# Power-Supplies.net
KiCad netlist of a schematic drawn in Altium Designer
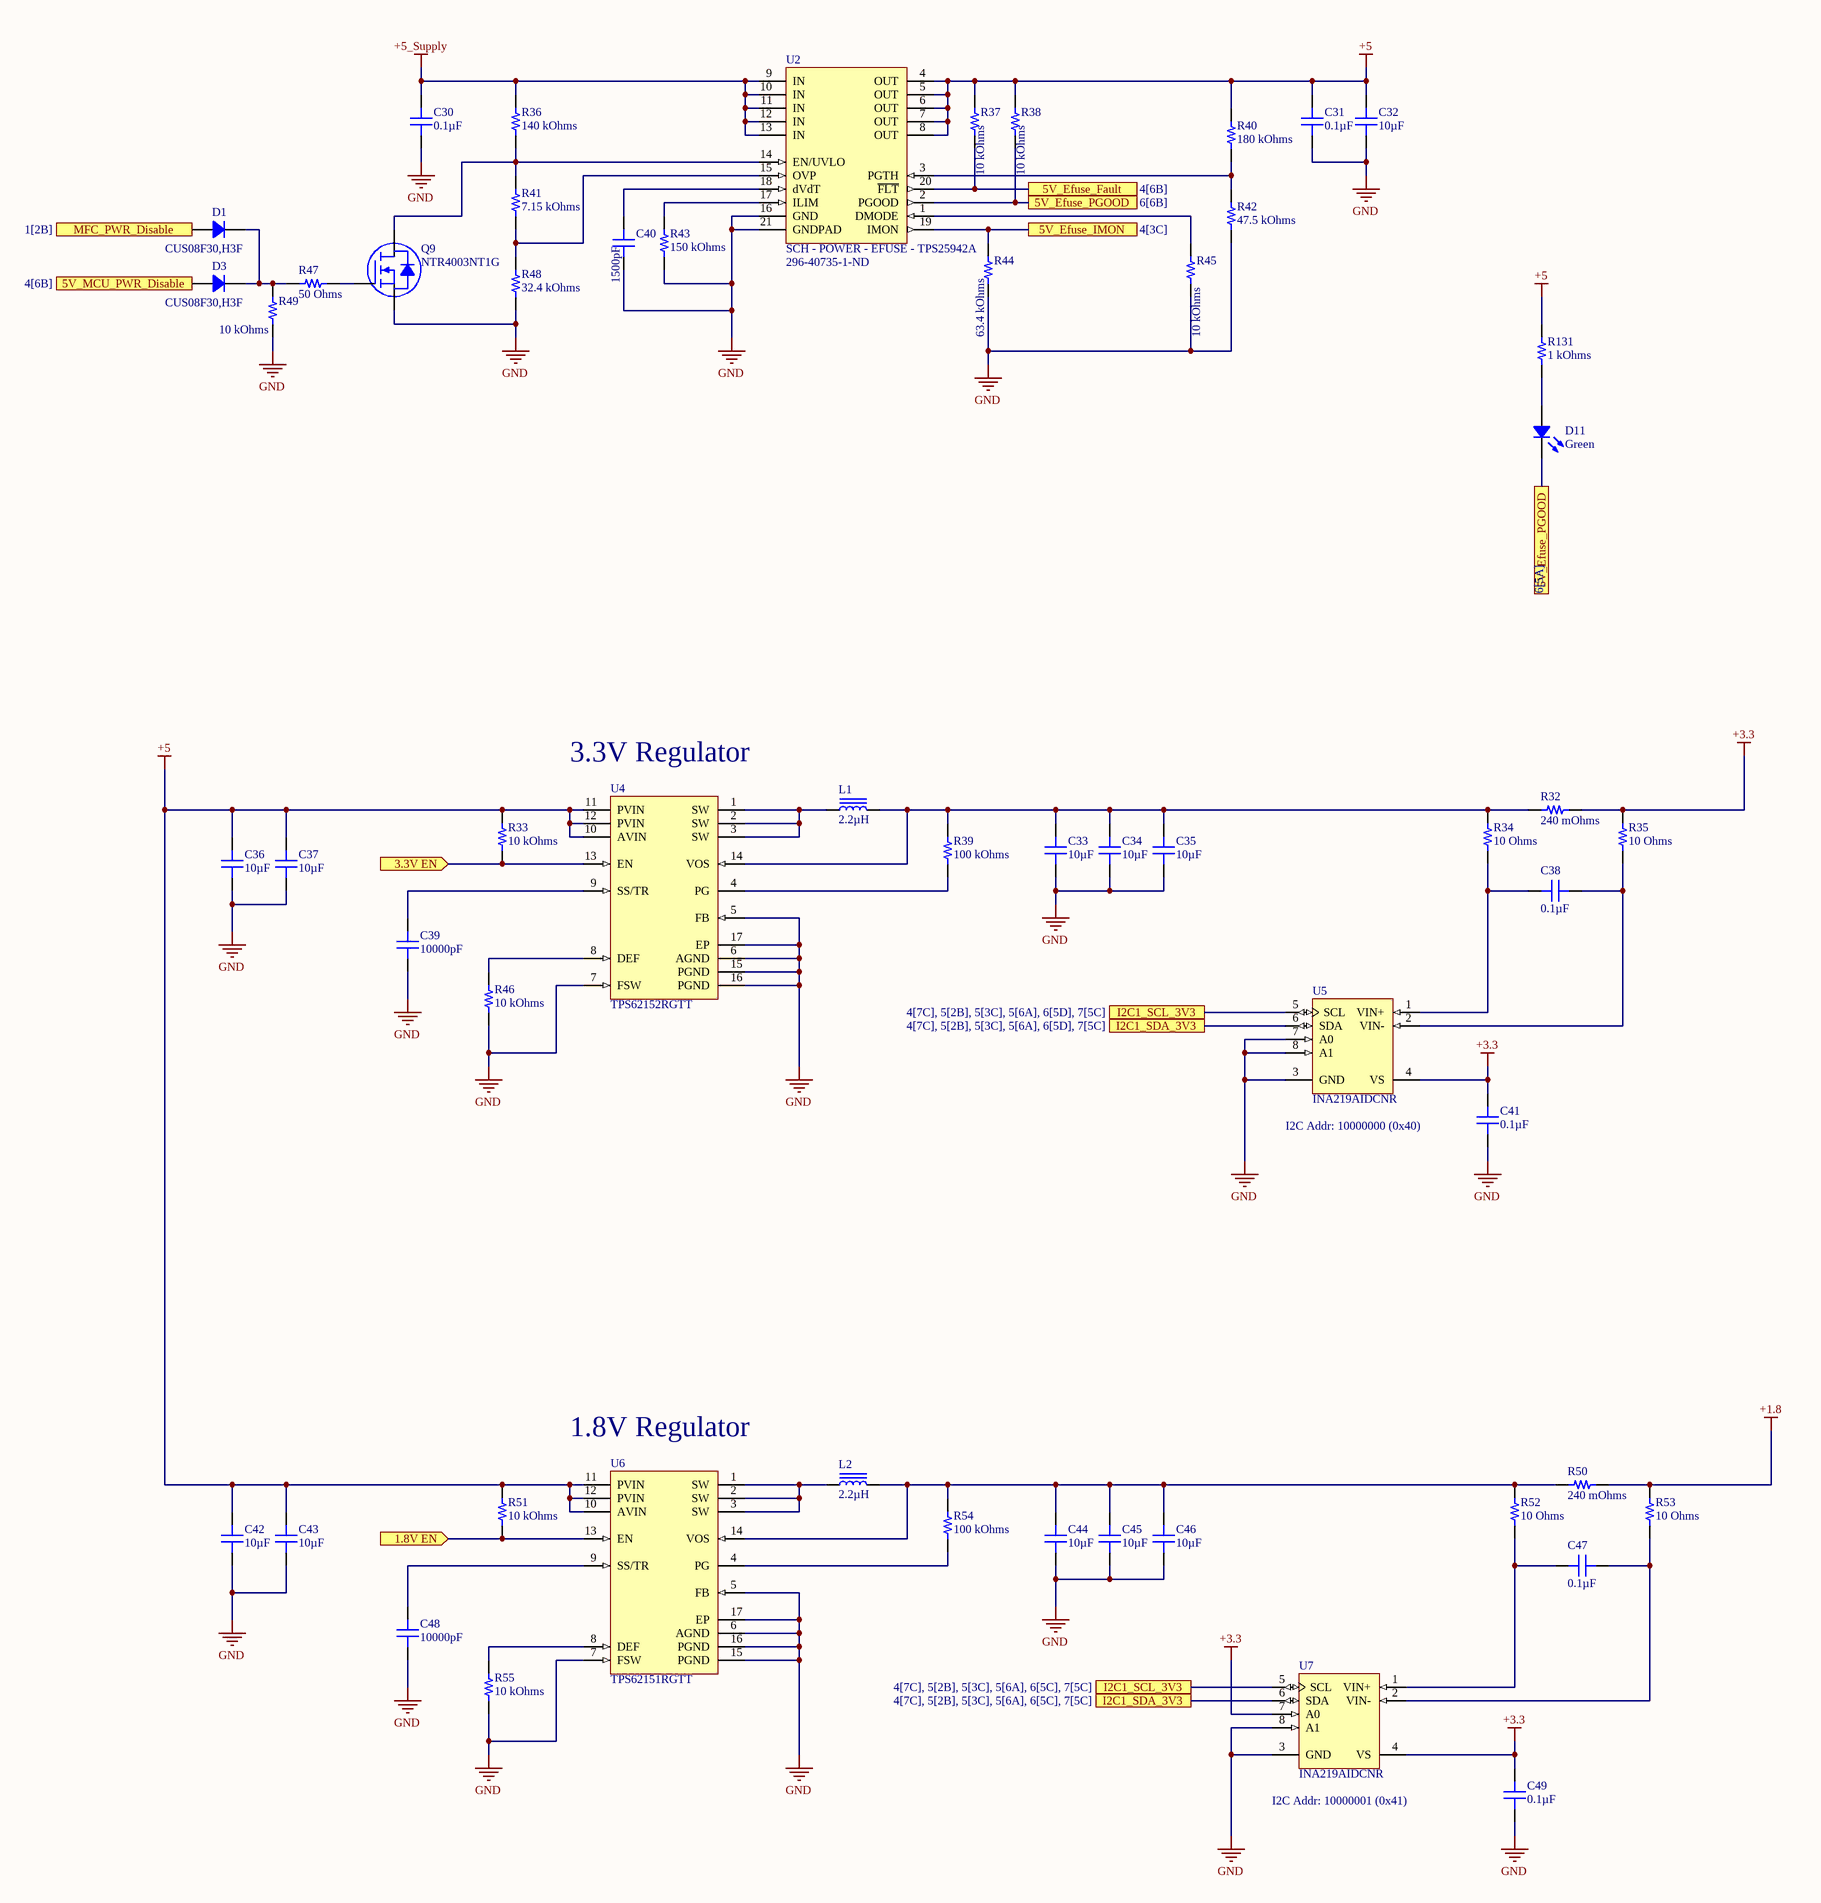
[diagram p0: Power-Supplies.SchDoc]

(export (version "E")
  (design (tool "Eeschema 10.0.6"))
  (components
    (comp (ref "C30")
      (value "0.1µF")
      (footprint "CAP 0603_1608")
      (description "CAP CER 0.1UF 25V X7R 0603")
      (fields
        (field (name "PART NUMBER") "CL10B104KA8WPNC")
        (field (name "MANUFACTURER") "Samsung Electro-Mechanics")
      )
      (libsource (lib "Celestial Altium Library - altium_library") (part "Capacitor"))
    )
    (comp (ref "C31")
      (value "0.1µF")
      (footprint "CAP 0603_1608")
      (description "CAP CER 0.1UF 25V X7R 0603")
      (fields
        (field (name "PART NUMBER") "CL10B104KA8WPNC")
        (field (name "MANUFACTURER") "Samsung Electro-Mechanics")
      )
      (libsource (lib "Celestial Altium Library - altium_library") (part "Capacitor"))
    )
    (comp (ref "C32")
      (value "10µF")
      (footprint "CAP 0805_2012")
      (description "CAP CER 10UF 16V X5R 0805")
      (fields (field (name "PART NUMBER") "CC0805KKX5R7BB106") (field (name "MANUFACTURER") "Yageo"))
      (libsource (lib "Celestial Altium Library - altium_library") (part "Capacitor"))
    )
    (comp (ref "C33")
      (value "10µF")
      (footprint "CAP 0805_2012")
      (description "CAP CER 10UF 16V X5R 0805")
      (fields (field (name "PART NUMBER") "CC0805KKX5R7BB106") (field (name "MANUFACTURER") "Yageo"))
      (libsource (lib "Celestial Altium Library - altium_library") (part "Capacitor"))
    )
    (comp (ref "C34")
      (value "10µF")
      (footprint "CAP 0805_2012")
      (description "CAP CER 10UF 16V X5R 0805")
      (fields (field (name "PART NUMBER") "CC0805KKX5R7BB106") (field (name "MANUFACTURER") "Yageo"))
      (libsource (lib "Celestial Altium Library - altium_library") (part "Capacitor"))
    )
    (comp (ref "C35")
      (value "10µF")
      (footprint "CAP 0805_2012")
      (description "CAP CER 10UF 16V X5R 0805")
      (fields (field (name "PART NUMBER") "CC0805KKX5R7BB106") (field (name "MANUFACTURER") "Yageo"))
      (libsource (lib "Celestial Altium Library - altium_library") (part "Capacitor"))
    )
    (comp (ref "C36")
      (value "10µF")
      (footprint "CAP 0805_2012")
      (description "CAP CER 10UF 16V X5R 0805")
      (fields (field (name "PART NUMBER") "CC0805KKX5R7BB106") (field (name "MANUFACTURER") "Yageo"))
      (libsource (lib "Celestial Altium Library - altium_library") (part "Capacitor"))
    )
    (comp (ref "C37")
      (value "10µF")
      (footprint "CAP 0805_2012")
      (description "CAP CER 10UF 16V X5R 0805")
      (fields (field (name "PART NUMBER") "CC0805KKX5R7BB106") (field (name "MANUFACTURER") "Yageo"))
      (libsource (lib "Celestial Altium Library - altium_library") (part "Capacitor"))
    )
    (comp (ref "C38")
      (value "0.1µF")
      (footprint "CAP 0603_1608")
      (description "CAP CER 0.1UF 25V X7R 0603")
      (fields
        (field (name "PART NUMBER") "CL10B104KA8WPNC")
        (field (name "MANUFACTURER") "Samsung Electro-Mechanics")
      )
      (libsource (lib "Celestial Altium Library - altium_library") (part "Capacitor"))
    )
    (comp (ref "C39")
      (value "10000pF")
      (footprint "CAP 0603_1608")
      (description "CAP CER 10000PF 16V X7R 0603")
      (fields (field (name "PART NUMBER") "C0603S103K4RACTU") (field (name "MANUFACTURER") "KEMET"))
      (libsource (lib "Celestial Altium Library - altium_library") (part "Capacitor"))
    )
    (comp (ref "C40")
      (value "1500pF")
      (footprint "CAP 0603_1608")
      (description "CAP CER 1500PF 25V X7R 0603")
      (fields (field (name "PART NUMBER") "CC0603JRX7R8BB152") (field (name "MANUFACTURER") "Yageo"))
      (libsource (lib "Celestial Altium Library - altium_library") (part "Capacitor"))
    )
    (comp (ref "C41")
      (value "0.1µF")
      (footprint "CAP 0603_1608")
      (description "CAP CER 0.1UF 25V X7R 0603")
      (fields
        (field (name "PART NUMBER") "CL10B104KA8WPNC")
        (field (name "MANUFACTURER") "Samsung Electro-Mechanics")
      )
      (libsource (lib "Celestial Altium Library - altium_library") (part "Capacitor"))
    )
    (comp (ref "C42")
      (value "10µF")
      (footprint "CAP 0805_2012")
      (description "CAP CER 10UF 16V X5R 0805")
      (fields (field (name "PART NUMBER") "CC0805KKX5R7BB106") (field (name "MANUFACTURER") "Yageo"))
      (libsource (lib "Celestial Altium Library - altium_library") (part "Capacitor"))
    )
    (comp (ref "C43")
      (value "10µF")
      (footprint "CAP 0805_2012")
      (description "CAP CER 10UF 16V X5R 0805")
      (fields (field (name "PART NUMBER") "CC0805KKX5R7BB106") (field (name "MANUFACTURER") "Yageo"))
      (libsource (lib "Celestial Altium Library - altium_library") (part "Capacitor"))
    )
    (comp (ref "C44")
      (value "10µF")
      (footprint "CAP 0805_2012")
      (description "CAP CER 10UF 16V X5R 0805")
      (fields (field (name "PART NUMBER") "CC0805KKX5R7BB106") (field (name "MANUFACTURER") "Yageo"))
      (libsource (lib "Celestial Altium Library - altium_library") (part "Capacitor"))
    )
    (comp (ref "C45")
      (value "10µF")
      (footprint "CAP 0805_2012")
      (description "CAP CER 10UF 16V X5R 0805")
      (fields (field (name "PART NUMBER") "CC0805KKX5R7BB106") (field (name "MANUFACTURER") "Yageo"))
      (libsource (lib "Celestial Altium Library - altium_library") (part "Capacitor"))
    )
    (comp (ref "C46")
      (value "10µF")
      (footprint "CAP 0805_2012")
      (description "CAP CER 10UF 16V X5R 0805")
      (fields (field (name "PART NUMBER") "CC0805KKX5R7BB106") (field (name "MANUFACTURER") "Yageo"))
      (libsource (lib "Celestial Altium Library - altium_library") (part "Capacitor"))
    )
    (comp (ref "C47")
      (value "0.1µF")
      (footprint "CAP 0603_1608")
      (description "CAP CER 0.1UF 25V X7R 0603")
      (fields
        (field (name "PART NUMBER") "CL10B104KA8WPNC")
        (field (name "MANUFACTURER") "Samsung Electro-Mechanics")
      )
      (libsource (lib "Celestial Altium Library - altium_library") (part "Capacitor"))
    )
    (comp (ref "C48")
      (value "10000pF")
      (footprint "CAP 0603_1608")
      (description "CAP CER 10000PF 16V X7R 0603")
      (fields (field (name "PART NUMBER") "C0603S103K4RACTU") (field (name "MANUFACTURER") "KEMET"))
      (libsource (lib "Celestial Altium Library - altium_library") (part "Capacitor"))
    )
    (comp (ref "C49")
      (value "0.1µF")
      (footprint "CAP 0603_1608")
      (description "CAP CER 0.1UF 25V X7R 0603")
      (fields
        (field (name "PART NUMBER") "CL10B104KA8WPNC")
        (field (name "MANUFACTURER") "Samsung Electro-Mechanics")
      )
      (libsource (lib "Celestial Altium Library - altium_library") (part "Capacitor"))
    )
    (comp (ref "D1")
      (value "CUS08F30,H3F")
      (footprint "SOD323")
      (description "DIODE SCHOTTKY 30V 800MA USC")
      (fields (field (name "MANUFACTURER") "Toshiba Semiconductor and Storage"))
      (libsource (lib "Celestial Altium Library - altium_library") (part "Diode"))
    )
    (comp (ref "D3")
      (value "CUS08F30,H3F")
      (footprint "SOD323")
      (description "DIODE SCHOTTKY 30V 800MA USC")
      (fields (field (name "MANUFACTURER") "Toshiba Semiconductor and Storage"))
      (libsource (lib "Celestial Altium Library - altium_library") (part "Diode"))
    )
    (comp (ref "D11")
      (value "Green")
      (footprint "LED 0603_1608 GREEN")
      (description "LED GREEN CLEAR CHIP SMD")
      (fields (field (name "PART NUMBER") "LTST-C193KGKT-5A") (field (name "MANUFACTURER") "Lite-On Inc."))
      (libsource (lib "Celestial Altium Library - altium_library") (part "LED"))
    )
    (comp (ref "L1")
      (value "2.2µH")
      (footprint "BOURNS SRN4018")
      (description "FIXED IND 2.2UH 2.9A 44 MOHM SMD")
      (fields (field (name "PART NUMBER") "SRN4018-2R2M") (field (name "MANUFACTURER") "Bourns Inc."))
      (libsource (lib "Celestial Altium Library - altium_library") (part "Inductor"))
    )
    (comp (ref "L2")
      (value "2.2µH")
      (footprint "BOURNS SRN4018")
      (description "FIXED IND 2.2UH 2.9A 44 MOHM SMD")
      (fields (field (name "PART NUMBER") "SRN4018-2R2M") (field (name "MANUFACTURER") "Bourns Inc."))
      (libsource (lib "Celestial Altium Library - altium_library") (part "Inductor"))
    )
    (comp (ref "Q9")
      (value "NTR4003NT1G")
      (footprint "ON SEMI SOT-23-3")
      (description "MOSFET N-CH 30V 500MA SOT-23")
      (fields (field (name "MANUFACTURER") "ON Semiconductor"))
      (libsource (lib "Celestial Altium Library - altium_library") (part "ON SEMI MOSFET N-CH SOT-23-3"))
    )
    (comp (ref "R32")
      (value "240 mOhms")
      (footprint "RES 0805_2012")
      (description "RES 0.24 OHM 1% 1/2W 0805")
      (fields
        (field (name "PART NUMBER") "ERJ-6DQFR24V")
        (field (name "MANUFACTURER") "Panasonic Electronic Components")
      )
      (libsource (lib "Celestial Altium Library - altium_library") (part "Resistor"))
    )
    (comp (ref "R33")
      (value "10 kOhms")
      (footprint "RES 0603_1608")
      (description "RES 10K OHM 5% 1/10W 0603")
      (fields
        (field (name "PART NUMBER") "RMCF0603JT10K0")
        (field (name "MANUFACTURER") "Stackpole Electronics Inc")
      )
      (libsource (lib "Celestial Altium Library - altium_library") (part "Resistor"))
    )
    (comp (ref "R34")
      (value "10 Ohms")
      (footprint "RES 0603_1608")
      (description "CRGCQ 0603 10R 1%")
      (fields
        (field (name "PART NUMBER") "CRGCQ0603F10R")
        (field (name "MANUFACTURER") "TE Connectivity Passive Product")
      )
      (libsource (lib "Celestial Altium Library - altium_library") (part "Resistor"))
    )
    (comp (ref "R35")
      (value "10 Ohms")
      (footprint "RES 0603_1608")
      (description "CRGCQ 0603 10R 1%")
      (fields
        (field (name "PART NUMBER") "CRGCQ0603F10R")
        (field (name "MANUFACTURER") "TE Connectivity Passive Product")
      )
      (libsource (lib "Celestial Altium Library - altium_library") (part "Resistor"))
    )
    (comp (ref "R36")
      (value "140 kOhms")
      (footprint "RES 0603_1608")
      (description "RES SMD 140K OHM 0.1% 1/10W 0603")
      (fields (field (name "PART NUMBER") "RT0603BRE07140KL") (field (name "MANUFACTURER") "Yageo"))
      (libsource (lib "Celestial Altium Library - altium_library") (part "Resistor"))
    )
    (comp (ref "R37")
      (value "10 kOhms")
      (footprint "RES 0603_1608")
      (description "RES 10K OHM 5% 1/10W 0603")
      (fields
        (field (name "PART NUMBER") "RMCF0603JT10K0")
        (field (name "MANUFACTURER") "Stackpole Electronics Inc")
      )
      (libsource (lib "Celestial Altium Library - altium_library") (part "Resistor"))
    )
    (comp (ref "R38")
      (value "10 kOhms")
      (footprint "RES 0603_1608")
      (description "RES 10K OHM 5% 1/10W 0603")
      (fields
        (field (name "PART NUMBER") "RMCF0603JT10K0")
        (field (name "MANUFACTURER") "Stackpole Electronics Inc")
      )
      (libsource (lib "Celestial Altium Library - altium_library") (part "Resistor"))
    )
    (comp (ref "R39")
      (value "100 kOhms")
      (footprint "RES 0603_1608")
      (description "RES SMD 100K OHM 5% 1/10W 0603")
      (fields (field (name "PART NUMBER") "RC0603JR-10100KL") (field (name "MANUFACTURER") "Yageo"))
      (libsource (lib "Celestial Altium Library - altium_library") (part "Resistor"))
    )
    (comp (ref "R40")
      (value "180 kOhms")
      (footprint "RES 0603_1608")
      (description "RES 180K OHM 1% 1/10W 0603")
      (fields
        (field (name "PART NUMBER") "RMCF0603FT180K")
        (field (name "MANUFACTURER") "Stackpole Electronics Inc")
      )
      (libsource (lib "Celestial Altium Library - altium_library") (part "Resistor"))
    )
    (comp (ref "R41")
      (value "7.15 kOhms")
      (footprint "RES 0603_1608")
      (description "RES SMD 7.15K OHM 0.1% 1/5W 0603")
      (fields
        (field (name "PART NUMBER") "ERJ-PB3B7151V")
        (field (name "MANUFACTURER") "Panasonic Electronic Components")
      )
      (libsource (lib "Celestial Altium Library - altium_library") (part "Resistor"))
    )
    (comp (ref "R42")
      (value "47.5 kOhms")
      (footprint "RES 0603_1608")
      (description "RES 47.5K OHM 1% 1/10W 0603")
      (fields
        (field (name "PART NUMBER") "RMCF0603FG47K5")
        (field (name "MANUFACTURER") "Stackpole Electronics Inc")
      )
      (libsource (lib "Celestial Altium Library - altium_library") (part "Resistor"))
    )
    (comp (ref "R43")
      (value "150 kOhms")
      (footprint "RES 0603_1608")
      (description "RES 150K OHM 1% 1/10W 0603")
      (fields
        (field (name "PART NUMBER") "RMCF0603FG150K")
        (field (name "MANUFACTURER") "Stackpole Electronics Inc")
      )
      (libsource (lib "Celestial Altium Library - altium_library") (part "Resistor"))
    )
    (comp (ref "R44")
      (value "63.4 kOhms")
      (footprint "RES 0603_1608")
      (description "RES 63.4K OHM 1% 1/10W 0603")
      (fields
        (field (name "PART NUMBER") "RMCF0603FT63K4")
        (field (name "MANUFACTURER") "Stackpole Electronics Inc")
      )
      (libsource (lib "Celestial Altium Library - altium_library") (part "Resistor"))
    )
    (comp (ref "R45")
      (value "10 kOhms")
      (footprint "RES 0603_1608")
      (description "RES 10K OHM 5% 1/10W 0603")
      (fields
        (field (name "PART NUMBER") "RMCF0603JT10K0")
        (field (name "MANUFACTURER") "Stackpole Electronics Inc")
      )
      (libsource (lib "Celestial Altium Library - altium_library") (part "Resistor"))
    )
    (comp (ref "R46")
      (value "10 kOhms")
      (footprint "RES 0603_1608")
      (description "RES 10K OHM 5% 1/10W 0603")
      (fields
        (field (name "PART NUMBER") "RMCF0603JT10K0")
        (field (name "MANUFACTURER") "Stackpole Electronics Inc")
      )
      (libsource (lib "Celestial Altium Library - altium_library") (part "Resistor"))
    )
    (comp (ref "R47")
      (value "50 Ohms")
      (footprint "RES 0603_1608")
      (description "RES SMD 50 OHM 1% 1/10W 0603")
      (fields (field (name "PART NUMBER") "CRCW060350R0FKEA") (field (name "MANUFACTURER") "Vishay Dale"))
      (libsource (lib "Celestial Altium Library - altium_library") (part "Resistor"))
    )
    (comp (ref "R48")
      (value "32.4 kOhms")
      (footprint "RES 0603_1608")
      (description "RES SMD 32.4K OHM 0.1% 1/5W 0603")
      (fields
        (field (name "PART NUMBER") "ERJ-PB3B3242V")
        (field (name "MANUFACTURER") "Panasonic Electronic Components")
      )
      (libsource (lib "Celestial Altium Library - altium_library") (part "Resistor"))
    )
    (comp (ref "R49")
      (value "10 kOhms")
      (footprint "RES 0603_1608")
      (description "RES 10K OHM 5% 1/10W 0603")
      (fields
        (field (name "PART NUMBER") "RMCF0603JT10K0")
        (field (name "MANUFACTURER") "Stackpole Electronics Inc")
      )
      (libsource (lib "Celestial Altium Library - altium_library") (part "Resistor"))
    )
    (comp (ref "R50")
      (value "240 mOhms")
      (footprint "RES 0805_2012")
      (description "RES 0.24 OHM 1% 1/2W 0805")
      (fields
        (field (name "PART NUMBER") "ERJ-6DQFR24V")
        (field (name "MANUFACTURER") "Panasonic Electronic Components")
      )
      (libsource (lib "Celestial Altium Library - altium_library") (part "Resistor"))
    )
    (comp (ref "R51")
      (value "10 kOhms")
      (footprint "RES 0603_1608")
      (description "RES 10K OHM 5% 1/10W 0603")
      (fields
        (field (name "PART NUMBER") "RMCF0603JT10K0")
        (field (name "MANUFACTURER") "Stackpole Electronics Inc")
      )
      (libsource (lib "Celestial Altium Library - altium_library") (part "Resistor"))
    )
    (comp (ref "R52")
      (value "10 Ohms")
      (footprint "RES 0603_1608")
      (description "CRGCQ 0603 10R 1%")
      (fields
        (field (name "PART NUMBER") "CRGCQ0603F10R")
        (field (name "MANUFACTURER") "TE Connectivity Passive Product")
      )
      (libsource (lib "Celestial Altium Library - altium_library") (part "Resistor"))
    )
    (comp (ref "R53")
      (value "10 Ohms")
      (footprint "RES 0603_1608")
      (description "CRGCQ 0603 10R 1%")
      (fields
        (field (name "PART NUMBER") "CRGCQ0603F10R")
        (field (name "MANUFACTURER") "TE Connectivity Passive Product")
      )
      (libsource (lib "Celestial Altium Library - altium_library") (part "Resistor"))
    )
    (comp (ref "R54")
      (value "100 kOhms")
      (footprint "RES 0603_1608")
      (description "RES SMD 100K OHM 5% 1/10W 0603")
      (fields (field (name "PART NUMBER") "RC0603JR-10100KL") (field (name "MANUFACTURER") "Yageo"))
      (libsource (lib "Celestial Altium Library - altium_library") (part "Resistor"))
    )
    (comp (ref "R55")
      (value "10 kOhms")
      (footprint "RES 0603_1608")
      (description "RES 10K OHM 5% 1/10W 0603")
      (fields
        (field (name "PART NUMBER") "RMCF0603JT10K0")
        (field (name "MANUFACTURER") "Stackpole Electronics Inc")
      )
      (libsource (lib "Celestial Altium Library - altium_library") (part "Resistor"))
    )
    (comp (ref "R131")
      (value "1 kOhms")
      (footprint "RES 0603_1608")
      (description "RES 1K OHM 1% 1/8W 0603")
      (fields
        (field (name "PART NUMBER") "RNCP0603FTD1K00")
        (field (name "MANUFACTURER") "Stackpole Electronics Inc")
      )
      (libsource (lib "Celestial Altium Library - altium_library") (part "Resistor"))
    )
    (comp (ref "U2")
      (value "SCH - POWER - EFUSE - TPS25942A")
      (footprint "PCB - LEADLESS - QFN - TI 20-WQFN")
      (fields (field (name "SUPPLIER PART NUMBER 1") "296-40735-1-ND"))
      (libsource (lib "HAB_ICs") (part "SCH - POWER - EFUSE - TPS25942A"))
    )
    (comp (ref "U4")
      (value "TPS62152RGTT")
      (footprint "RGT0016C_V")
      (fields (field (name "MANUFACTURER") "Texas Instruments"))
      (libsource (lib "Altium Content Vault") (part "TI-TPS62152RGT16-1700X1700TP"))
    )
    (comp (ref "U5")
      (value "INA219AIDCNR")
      (footprint "DCN0008A_M")
      (fields (field (name "MANUFACTURER") "Texas Instruments"))
      (libsource (lib "Altium Content Vault") (part "TI-INA219DCN8"))
    )
    (comp (ref "U6")
      (value "TPS62151RGTT")
      (footprint "RGT0016C_V")
      (fields (field (name "MANUFACTURER") "Texas Instruments"))
      (libsource (lib "Altium Content Vault") (part "TI-TPS62151RGT16-1700X1700TP"))
    )
    (comp (ref "U7")
      (value "INA219AIDCNR")
      (footprint "DCN0008A_M")
      (fields (field (name "MANUFACTURER") "Texas Instruments"))
      (libsource (lib "Altium Content Vault") (part "TI-INA219DCN8"))
    )
  )
  (nets
    (net (code "1") (name "+1.8") (class "Default")
      (node (ref "R50") (pin "2") (pinfunction "2_2") (pintype "passive"))
      (node (ref "R53") (pin "2") (pinfunction "2_2") (pintype "passive"))
    )
    (net (code "2") (name "+3.3") (class "Default")
      (node (ref "C41") (pin "2") (pinfunction "2_2") (pintype "passive"))
      (node (ref "C49") (pin "2") (pinfunction "2_2") (pintype "passive"))
      (node (ref "R32") (pin "2") (pinfunction "2_2") (pintype "passive"))
      (node (ref "R35") (pin "2") (pinfunction "2_2") (pintype "passive"))
      (node (ref "U5") (pin "4") (pinfunction "VS_4") (pintype "power_in"))
      (node (ref "U7") (pin "4") (pinfunction "VS_4") (pintype "power_in"))
      (node (ref "U7") (pin "7") (pinfunction "A0_7") (pintype "input"))
    )
    (net (code "3") (name "+5") (class "Default")
      (node (ref "C31") (pin "2") (pinfunction "2_2") (pintype "passive"))
      (node (ref "C32") (pin "2") (pinfunction "2_2") (pintype "passive"))
      (node (ref "C36") (pin "2") (pinfunction "2_2") (pintype "passive"))
      (node (ref "C37") (pin "2") (pinfunction "2_2") (pintype "passive"))
      (node (ref "C42") (pin "2") (pinfunction "2_2") (pintype "passive"))
      (node (ref "C43") (pin "2") (pinfunction "2_2") (pintype "passive"))
      (node (ref "R131") (pin "1") (pinfunction "1_1") (pintype "passive"))
      (node (ref "R33") (pin "2") (pinfunction "2_2") (pintype "passive"))
      (node (ref "R37") (pin "2") (pinfunction "2_2") (pintype "passive"))
      (node (ref "R38") (pin "2") (pinfunction "2_2") (pintype "passive"))
      (node (ref "R40") (pin "2") (pinfunction "2_2") (pintype "passive"))
      (node (ref "R51") (pin "2") (pinfunction "2_2") (pintype "passive"))
      (node (ref "U2") (pin "4") (pinfunction "OUT_4") (pintype "power_in"))
      (node (ref "U2") (pin "5") (pinfunction "OUT_5") (pintype "power_in"))
      (node (ref "U2") (pin "6") (pinfunction "OUT_6") (pintype "power_in"))
      (node (ref "U2") (pin "7") (pinfunction "OUT_7") (pintype "power_in"))
      (node (ref "U2") (pin "8") (pinfunction "OUT_8") (pintype "power_in"))
      (node (ref "U4") (pin "10") (pinfunction "AVIN_10") (pintype "power_in"))
      (node (ref "U4") (pin "11") (pinfunction "PVIN_11") (pintype "power_in"))
      (node (ref "U4") (pin "12") (pinfunction "PVIN_12") (pintype "power_in"))
      (node (ref "U6") (pin "10") (pinfunction "AVIN_10") (pintype "power_in"))
      (node (ref "U6") (pin "11") (pinfunction "PVIN_11") (pintype "power_in"))
      (node (ref "U6") (pin "12") (pinfunction "PVIN_12") (pintype "power_in"))
    )
    (net (code "4") (name "+5_Supply") (class "Default")
      (node (ref "C30") (pin "2") (pinfunction "2_2") (pintype "passive"))
      (node (ref "R36") (pin "2") (pinfunction "2_2") (pintype "passive"))
      (node (ref "U2") (pin "10") (pinfunction "IN_10") (pintype "power_in"))
      (node (ref "U2") (pin "11") (pinfunction "IN_11") (pintype "power_in"))
      (node (ref "U2") (pin "12") (pinfunction "IN_12") (pintype "power_in"))
      (node (ref "U2") (pin "13") (pinfunction "IN_13") (pintype "power_in"))
      (node (ref "U2") (pin "9") (pinfunction "IN_9") (pintype "power_in"))
    )
    (net (code "5") (name "/1.8V EN") (class "Default")
      (node (ref "R51") (pin "1") (pinfunction "1_1") (pintype "passive"))
      (node (ref "U6") (pin "13") (pinfunction "EN_13") (pintype "input"))
    )
    (net (code "6") (name "/3.3V EN") (class "Default")
      (node (ref "R33") (pin "1") (pinfunction "1_1") (pintype "passive"))
      (node (ref "U4") (pin "13") (pinfunction "EN_13") (pintype "input"))
    )
    (net (code "7") (name "/5V_Efuse_Fault") (class "Default")
      (node (ref "R37") (pin "1") (pinfunction "1_1") (pintype "passive"))
      (node (ref "U2") (pin "20") (pinfunction "~{FLT}_20") (pintype "output"))
    )
    (net (code "8") (name "/5V_Efuse_IMON") (class "Default")
      (node (ref "R44") (pin "2") (pinfunction "2_2") (pintype "passive"))
      (node (ref "U2") (pin "19") (pinfunction "IMON_19") (pintype "output"))
    )
    (net (code "9") (name "/5V_Efuse_PGOOD") (class "Default")
      (node (ref "D11") (pin "2") (pinfunction "2_2") (pintype "passive"))
      (node (ref "R38") (pin "1") (pinfunction "1_1") (pintype "passive"))
      (node (ref "U2") (pin "2") (pinfunction "PGOOD_2") (pintype "output"))
    )
    (net (code "10") (name "/5V_MCU_PWR_Disable") (class "Default")
      (node (ref "D3") (pin "1") (pinfunction "1_1") (pintype "passive"))
    )
    (net (code "11") (name "/I2C1_SCL_3V3") (class "Default")
      (node (ref "U5") (pin "5") (pinfunction "SCL_5") (pintype "bidirectional"))
      (node (ref "U7") (pin "5") (pinfunction "SCL_5") (pintype "bidirectional"))
    )
    (net (code "12") (name "/I2C1_SDA_3V3") (class "Default")
      (node (ref "U5") (pin "6") (pinfunction "SDA_6") (pintype "bidirectional"))
      (node (ref "U7") (pin "6") (pinfunction "SDA_6") (pintype "bidirectional"))
    )
    (net (code "13") (name "/MFC_PWR_Disable") (class "Default")
      (node (ref "D1") (pin "1") (pinfunction "1_1") (pintype "passive"))
    )
    (net (code "14") (name "GND") (class "Default")
      (node (ref "C30") (pin "1") (pinfunction "1_1") (pintype "passive"))
      (node (ref "C31") (pin "1") (pinfunction "1_1") (pintype "passive"))
      (node (ref "C32") (pin "1") (pinfunction "1_1") (pintype "passive"))
      (node (ref "C33") (pin "1") (pinfunction "1_1") (pintype "passive"))
      (node (ref "C34") (pin "1") (pinfunction "1_1") (pintype "passive"))
      (node (ref "C35") (pin "1") (pinfunction "1_1") (pintype "passive"))
      (node (ref "C36") (pin "1") (pinfunction "1_1") (pintype "passive"))
      (node (ref "C37") (pin "1") (pinfunction "1_1") (pintype "passive"))
      (node (ref "C39") (pin "1") (pinfunction "1_1") (pintype "passive"))
      (node (ref "C40") (pin "1") (pinfunction "1_1") (pintype "passive"))
      (node (ref "C41") (pin "1") (pinfunction "1_1") (pintype "passive"))
      (node (ref "C42") (pin "1") (pinfunction "1_1") (pintype "passive"))
      (node (ref "C43") (pin "1") (pinfunction "1_1") (pintype "passive"))
      (node (ref "C44") (pin "1") (pinfunction "1_1") (pintype "passive"))
      (node (ref "C45") (pin "1") (pinfunction "1_1") (pintype "passive"))
      (node (ref "C46") (pin "1") (pinfunction "1_1") (pintype "passive"))
      (node (ref "C48") (pin "1") (pinfunction "1_1") (pintype "passive"))
      (node (ref "C49") (pin "1") (pinfunction "1_1") (pintype "passive"))
      (node (ref "Q9") (pin "2") (pinfunction "S_2") (pintype "passive"))
      (node (ref "R42") (pin "1") (pinfunction "1_1") (pintype "passive"))
      (node (ref "R43") (pin "1") (pinfunction "1_1") (pintype "passive"))
      (node (ref "R44") (pin "1") (pinfunction "1_1") (pintype "passive"))
      (node (ref "R45") (pin "1") (pinfunction "1_1") (pintype "passive"))
      (node (ref "R46") (pin "1") (pinfunction "1_1") (pintype "passive"))
      (node (ref "R48") (pin "1") (pinfunction "1_1") (pintype "passive"))
      (node (ref "R49") (pin "1") (pinfunction "1_1") (pintype "passive"))
      (node (ref "R55") (pin "1") (pinfunction "1_1") (pintype "passive"))
      (node (ref "U2") (pin "16") (pinfunction "GND_16") (pintype "power_in"))
      (node (ref "U2") (pin "21") (pinfunction "GNDPAD_21") (pintype "power_in"))
      (node (ref "U4") (pin "15") (pinfunction "PGND_15") (pintype "power_in"))
      (node (ref "U4") (pin "16") (pinfunction "PGND_16") (pintype "power_in"))
      (node (ref "U4") (pin "17") (pinfunction "EP_17") (pintype "power_in"))
      (node (ref "U4") (pin "5") (pinfunction "FB_5") (pintype "input"))
      (node (ref "U4") (pin "6") (pinfunction "AGND_6") (pintype "power_in"))
      (node (ref "U4") (pin "7") (pinfunction "FSW_7") (pintype "input"))
      (node (ref "U5") (pin "3") (pinfunction "GND_3") (pintype "power_in"))
      (node (ref "U5") (pin "7") (pinfunction "A0_7") (pintype "input"))
      (node (ref "U5") (pin "8") (pinfunction "A1_8") (pintype "input"))
      (node (ref "U6") (pin "15") (pinfunction "PGND_15") (pintype "power_in"))
      (node (ref "U6") (pin "16") (pinfunction "PGND_16") (pintype "power_in"))
      (node (ref "U6") (pin "17") (pinfunction "EP_17") (pintype "power_in"))
      (node (ref "U6") (pin "5") (pinfunction "FB_5") (pintype "input"))
      (node (ref "U6") (pin "6") (pinfunction "AGND_6") (pintype "power_in"))
      (node (ref "U6") (pin "7") (pinfunction "FSW_7") (pintype "input"))
      (node (ref "U7") (pin "3") (pinfunction "GND_3") (pintype "power_in"))
      (node (ref "U7") (pin "8") (pinfunction "A1_8") (pintype "input"))
    )
    (net (code "15") (name "Net-(D1-Pad2)") (class "Default")
      (node (ref "D1") (pin "2") (pinfunction "2_2") (pintype "passive"))
      (node (ref "D3") (pin "2") (pinfunction "2_2") (pintype "passive"))
      (node (ref "R47") (pin "2") (pinfunction "2_2") (pintype "passive"))
      (node (ref "R49") (pin "2") (pinfunction "2_2") (pintype "passive"))
    )
    (net (code "16") (name "Net-(D11-Pad1)") (class "Default")
      (node (ref "D11") (pin "1") (pinfunction "1_1") (pintype "passive"))
      (node (ref "R131") (pin "2") (pinfunction "2_2") (pintype "passive"))
    )
    (net (code "17") (name "Net-(L1-Pad1)") (class "Default")
      (node (ref "L1") (pin "1") (pinfunction "1_1") (pintype "passive"))
      (node (ref "U4") (pin "1") (pinfunction "SW_1") (pintype "power_in"))
      (node (ref "U4") (pin "2") (pinfunction "SW_2") (pintype "power_in"))
      (node (ref "U4") (pin "3") (pinfunction "SW_3") (pintype "power_in"))
    )
    (net (code "18") (name "Net-(L2-Pad1)") (class "Default")
      (node (ref "L2") (pin "1") (pinfunction "1_1") (pintype "passive"))
      (node (ref "U6") (pin "1") (pinfunction "SW_1") (pintype "power_in"))
      (node (ref "U6") (pin "2") (pinfunction "SW_2") (pintype "power_in"))
      (node (ref "U6") (pin "3") (pinfunction "SW_3") (pintype "power_in"))
    )
    (net (code "19") (name "Net-(Q9-D)") (class "Default")
      (node (ref "Q9") (pin "3") (pinfunction "D_3") (pintype "passive"))
      (node (ref "R36") (pin "1") (pinfunction "1_1") (pintype "passive"))
      (node (ref "R41") (pin "2") (pinfunction "2_2") (pintype "passive"))
      (node (ref "U2") (pin "14") (pinfunction "EN/UVLO_14") (pintype "input"))
    )
    (net (code "20") (name "Net-(Q9-G)") (class "Default")
      (node (ref "Q9") (pin "1") (pinfunction "G_1") (pintype "passive"))
      (node (ref "R47") (pin "1") (pinfunction "1_1") (pintype "passive"))
    )
    (net (code "21") (name "Net-(U2-DMODE)") (class "Default")
      (node (ref "R45") (pin "2") (pinfunction "2_2") (pintype "passive"))
      (node (ref "U2") (pin "1") (pinfunction "DMODE_1") (pintype "input"))
    )
    (net (code "22") (name "Net-(U2-ILIM)") (class "Default")
      (node (ref "R43") (pin "2") (pinfunction "2_2") (pintype "passive"))
      (node (ref "U2") (pin "17") (pinfunction "ILIM_17") (pintype "input"))
    )
    (net (code "23") (name "Net-(U2-OVP)") (class "Default")
      (node (ref "R41") (pin "1") (pinfunction "1_1") (pintype "passive"))
      (node (ref "R48") (pin "2") (pinfunction "2_2") (pintype "passive"))
      (node (ref "U2") (pin "15") (pinfunction "OVP_15") (pintype "input"))
    )
    (net (code "24") (name "Net-(U2-PGTH)") (class "Default")
      (node (ref "R40") (pin "1") (pinfunction "1_1") (pintype "passive"))
      (node (ref "R42") (pin "2") (pinfunction "2_2") (pintype "passive"))
      (node (ref "U2") (pin "3") (pinfunction "PGTH_3") (pintype "input"))
    )
    (net (code "25") (name "Net-(U2-dVdT)") (class "Default")
      (node (ref "C40") (pin "2") (pinfunction "2_2") (pintype "passive"))
      (node (ref "U2") (pin "18") (pinfunction "dVdT_18") (pintype "input"))
    )
    (net (code "26") (name "Net-(U4-DEF)") (class "Default")
      (node (ref "R46") (pin "2") (pinfunction "2_2") (pintype "passive"))
      (node (ref "U4") (pin "8") (pinfunction "DEF_8") (pintype "input"))
    )
    (net (code "27") (name "Net-(U4-PG)") (class "Default")
      (node (ref "R39") (pin "1") (pinfunction "1_1") (pintype "passive"))
      (node (ref "U4") (pin "4") (pinfunction "PG_4") (pintype "tri_state"))
    )
    (net (code "28") (name "Net-(U4-SS{slash}TR)") (class "Default")
      (node (ref "C39") (pin "2") (pinfunction "2_2") (pintype "passive"))
      (node (ref "U4") (pin "9") (pinfunction "SS/TR_9") (pintype "input"))
    )
    (net (code "29") (name "Net-(U4-VOS)") (class "Default")
      (node (ref "C33") (pin "2") (pinfunction "2_2") (pintype "passive"))
      (node (ref "C34") (pin "2") (pinfunction "2_2") (pintype "passive"))
      (node (ref "C35") (pin "2") (pinfunction "2_2") (pintype "passive"))
      (node (ref "L1") (pin "2") (pinfunction "2_2") (pintype "passive"))
      (node (ref "R32") (pin "1") (pinfunction "1_1") (pintype "passive"))
      (node (ref "R34") (pin "2") (pinfunction "2_2") (pintype "passive"))
      (node (ref "R39") (pin "2") (pinfunction "2_2") (pintype "passive"))
      (node (ref "U4") (pin "14") (pinfunction "VOS_14") (pintype "input"))
    )
    (net (code "30") (name "Net-(U5-VIN+)") (class "Default")
      (node (ref "C38") (pin "2") (pinfunction "2_2") (pintype "passive"))
      (node (ref "R34") (pin "1") (pinfunction "1_1") (pintype "passive"))
      (node (ref "U5") (pin "1") (pinfunction "VIN+_1") (pintype "input"))
    )
    (net (code "31") (name "Net-(U5-VIN-)") (class "Default")
      (node (ref "C38") (pin "1") (pinfunction "1_1") (pintype "passive"))
      (node (ref "R35") (pin "1") (pinfunction "1_1") (pintype "passive"))
      (node (ref "U5") (pin "2") (pinfunction "VIN-_2") (pintype "input"))
    )
    (net (code "32") (name "Net-(U6-DEF)") (class "Default")
      (node (ref "R55") (pin "2") (pinfunction "2_2") (pintype "passive"))
      (node (ref "U6") (pin "8") (pinfunction "DEF_8") (pintype "input"))
    )
    (net (code "33") (name "Net-(U6-PG)") (class "Default")
      (node (ref "R54") (pin "1") (pinfunction "1_1") (pintype "passive"))
      (node (ref "U6") (pin "4") (pinfunction "PG_4") (pintype "tri_state"))
    )
    (net (code "34") (name "Net-(U6-SS{slash}TR)") (class "Default")
      (node (ref "C48") (pin "2") (pinfunction "2_2") (pintype "passive"))
      (node (ref "U6") (pin "9") (pinfunction "SS/TR_9") (pintype "input"))
    )
    (net (code "35") (name "Net-(U6-VOS)") (class "Default")
      (node (ref "C44") (pin "2") (pinfunction "2_2") (pintype "passive"))
      (node (ref "C45") (pin "2") (pinfunction "2_2") (pintype "passive"))
      (node (ref "C46") (pin "2") (pinfunction "2_2") (pintype "passive"))
      (node (ref "L2") (pin "2") (pinfunction "2_2") (pintype "passive"))
      (node (ref "R50") (pin "1") (pinfunction "1_1") (pintype "passive"))
      (node (ref "R52") (pin "2") (pinfunction "2_2") (pintype "passive"))
      (node (ref "R54") (pin "2") (pinfunction "2_2") (pintype "passive"))
      (node (ref "U6") (pin "14") (pinfunction "VOS_14") (pintype "input"))
    )
    (net (code "36") (name "Net-(U7-VIN+)") (class "Default")
      (node (ref "C47") (pin "2") (pinfunction "2_2") (pintype "passive"))
      (node (ref "R52") (pin "1") (pinfunction "1_1") (pintype "passive"))
      (node (ref "U7") (pin "1") (pinfunction "VIN+_1") (pintype "input"))
    )
    (net (code "37") (name "Net-(U7-VIN-)") (class "Default")
      (node (ref "C47") (pin "1") (pinfunction "1_1") (pintype "passive"))
      (node (ref "R53") (pin "1") (pinfunction "1_1") (pintype "passive"))
      (node (ref "U7") (pin "2") (pinfunction "VIN-_2") (pintype "input"))
    )
  )
)
